# sensorBoard.net
KiCad netlist of a schematic drawn in EAGLE
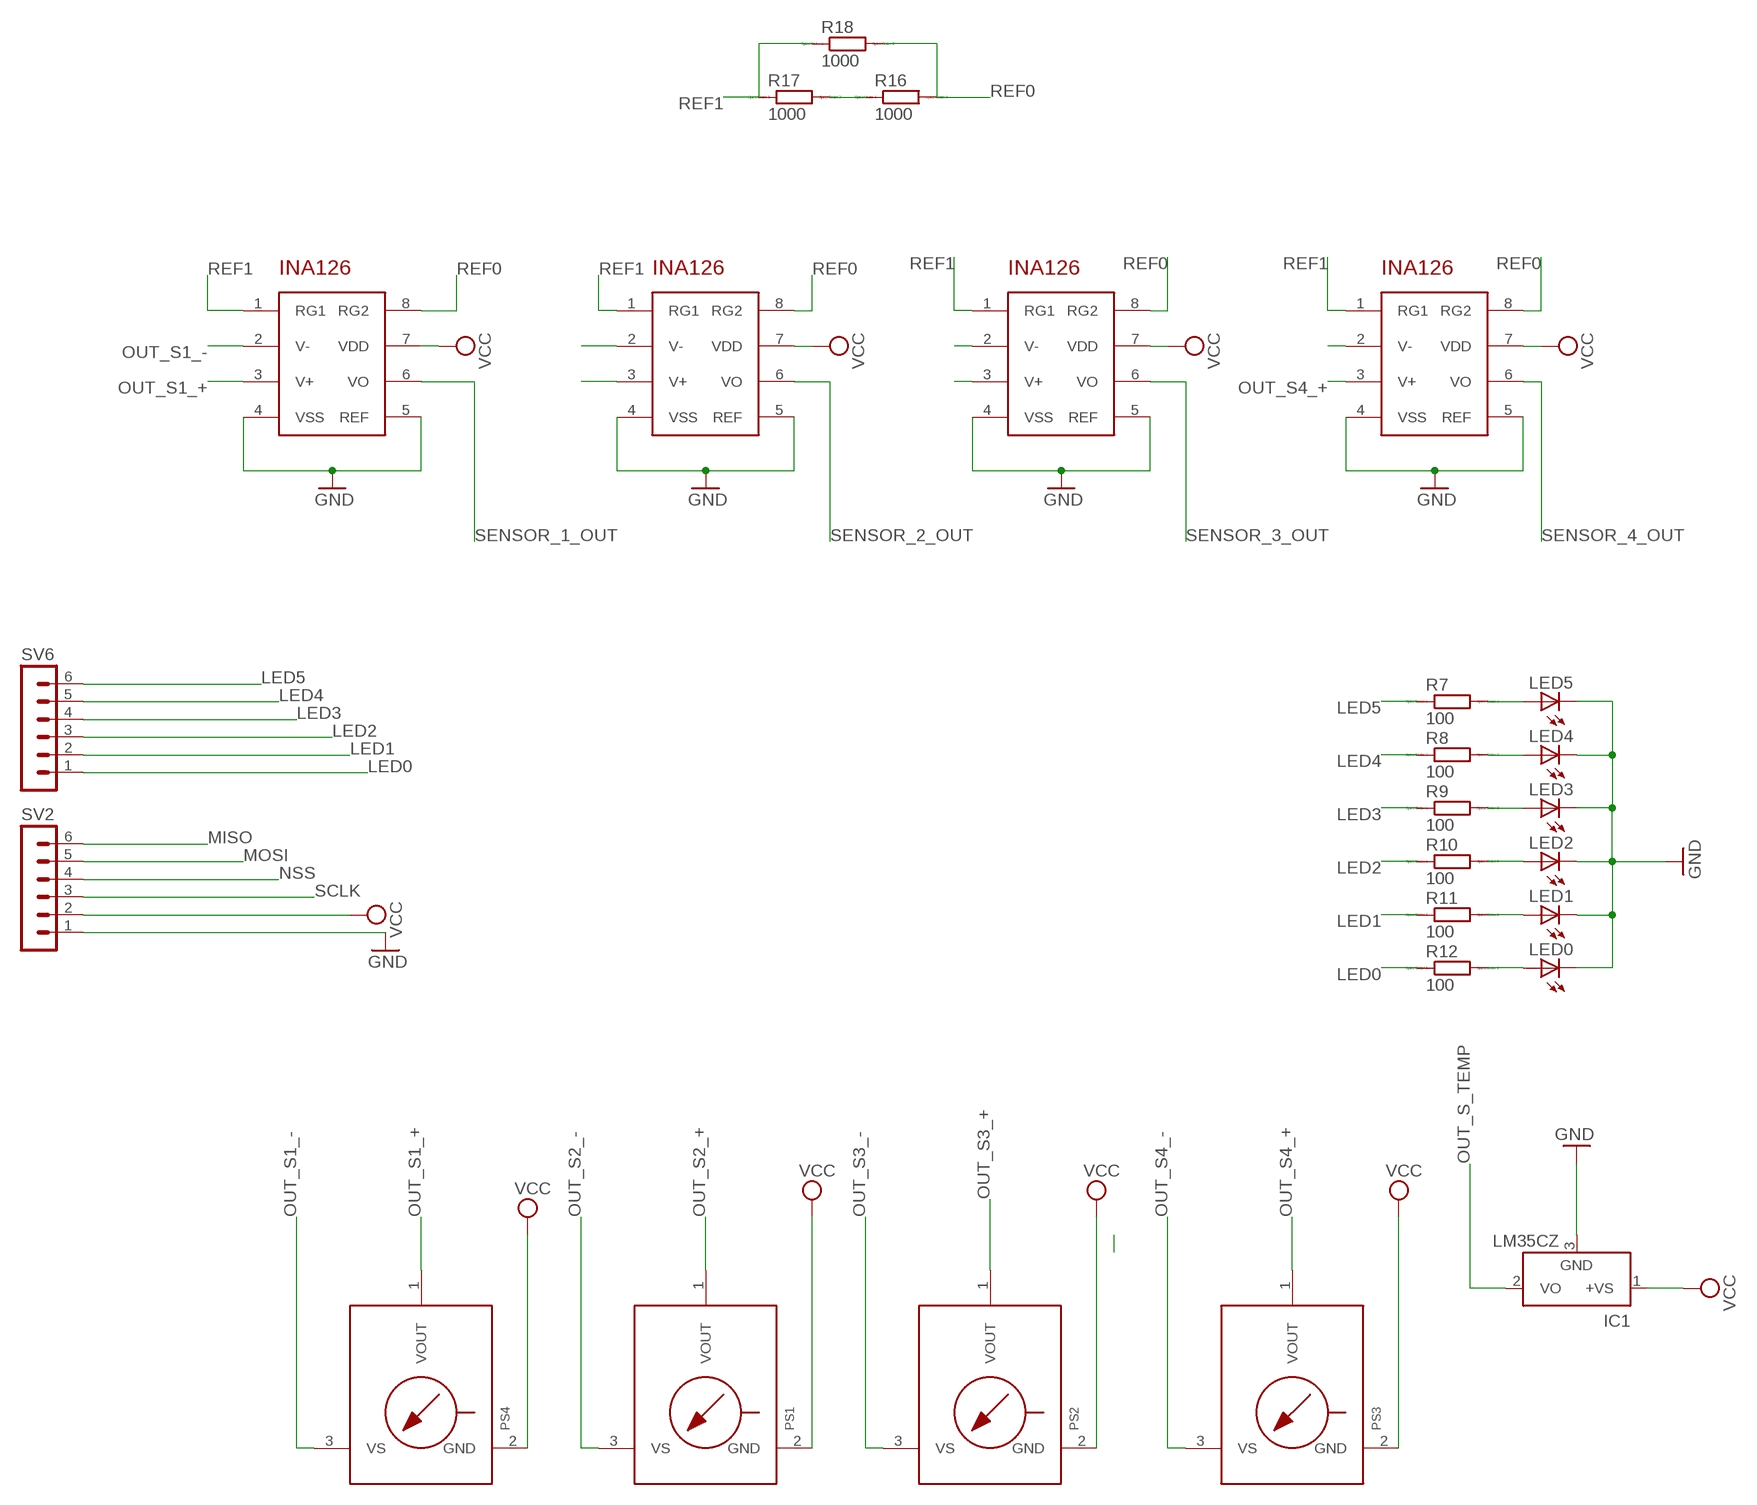
[diagram p0: schematic, sheet 1]

(export (version "E")
  (design (tool "Eeschema 10.0.6"))
  (components
    (comp (ref "IC1")
      (value "LM35CZ")
      (footprint "eagle-import:TO92")
      (libsource (lib "eagle-import") (part "LM35CZ"))
    )
    (comp (ref "LED0")
      (value "LED3MM")
      (footprint "eagle-import:LED3MM")
      (libsource (lib "eagle-import") (part "LED3MM"))
    )
    (comp (ref "LED1")
      (value "LED3MM")
      (footprint "eagle-import:LED3MM")
      (libsource (lib "eagle-import") (part "LED3MM"))
    )
    (comp (ref "LED2")
      (value "LED3MM")
      (footprint "eagle-import:LED3MM")
      (libsource (lib "eagle-import") (part "LED3MM"))
    )
    (comp (ref "LED3")
      (value "LED3MM")
      (footprint "eagle-import:LED3MM")
      (libsource (lib "eagle-import") (part "LED3MM"))
    )
    (comp (ref "LED4")
      (value "LED3MM")
      (footprint "eagle-import:LED3MM")
      (libsource (lib "eagle-import") (part "LED3MM"))
    )
    (comp (ref "LED5")
      (value "LED3MM")
      (footprint "eagle-import:LED3MM")
      (libsource (lib "eagle-import") (part "LED3MM"))
    )
    (comp (ref "PS1")
      (value "MPX-867B-H")
      (footprint "eagle-import:867B-H")
      (libsource (lib "eagle-import") (part "MPX-867B-H"))
    )
    (comp (ref "PS2")
      (value "MPX-867B-H")
      (footprint "eagle-import:867B-H")
      (libsource (lib "eagle-import") (part "MPX-867B-H"))
    )
    (comp (ref "PS3")
      (value "MPX-867B-H")
      (footprint "eagle-import:867B-H")
      (libsource (lib "eagle-import") (part "MPX-867B-H"))
    )
    (comp (ref "PS4")
      (value "MPX-867B-H")
      (footprint "eagle-import:867B-H")
      (libsource (lib "eagle-import") (part "MPX-867B-H"))
    )
    (comp (ref "R7")
      (value "100")
      (footprint "eagle-import:0207_10")
      (libsource (lib "eagle-import") (part "R0207/10"))
    )
    (comp (ref "R8")
      (value "100")
      (footprint "eagle-import:0207_10")
      (libsource (lib "eagle-import") (part "R0207/10"))
    )
    (comp (ref "R9")
      (value "100")
      (footprint "eagle-import:0207_10")
      (libsource (lib "eagle-import") (part "R0207/10"))
    )
    (comp (ref "R10")
      (value "100")
      (footprint "eagle-import:0207_10")
      (libsource (lib "eagle-import") (part "R0207/10"))
    )
    (comp (ref "R11")
      (value "100")
      (footprint "eagle-import:0207_10")
      (libsource (lib "eagle-import") (part "R0207/10"))
    )
    (comp (ref "R12")
      (value "100")
      (footprint "eagle-import:0207_10")
      (libsource (lib "eagle-import") (part "R0207/10"))
    )
    (comp (ref "R16")
      (value "1000")
      (footprint "eagle-import:0207_10")
      (libsource (lib "eagle-import") (part "R0207/10"))
    )
    (comp (ref "R17")
      (value "1000")
      (footprint "eagle-import:0207_10")
      (libsource (lib "eagle-import") (part "R0207/10"))
    )
    (comp (ref "R18")
      (value "1000")
      (footprint "eagle-import:0207_10")
      (libsource (lib "eagle-import") (part "R0207/10"))
    )
    (comp (ref "SV2")
      (value "MA06-1")
      (footprint "eagle-import:MA06-1")
      (libsource (lib "eagle-import") (part "MA06-1"))
    )
    (comp (ref "SV6")
      (value "MA06-1")
      (footprint "eagle-import:MA06-1")
      (libsource (lib "eagle-import") (part "MA06-1"))
    )
    (comp (ref "U$1")
      (value "INA126")
      (footprint "eagle-import:SO-08")
      (libsource (lib "eagle-import") (part "INA126"))
    )
    (comp (ref "U$2")
      (value "INA126")
      (footprint "eagle-import:SO-08")
      (libsource (lib "eagle-import") (part "INA126"))
    )
    (comp (ref "U$3")
      (value "INA126")
      (footprint "eagle-import:SO-08")
      (libsource (lib "eagle-import") (part "INA126"))
    )
    (comp (ref "U$4")
      (value "INA126")
      (footprint "eagle-import:SO-08")
      (libsource (lib "eagle-import") (part "INA126"))
    )
  )
  (nets
    (net (code "1") (name "/LED0") (class "Default")
      (node (ref "R12") (pin "1") (pinfunction "1_1") (pintype "passive"))
      (node (ref "SV6") (pin "1") (pinfunction "1_1") (pintype "passive"))
    )
    (net (code "2") (name "/LED1") (class "Default")
      (node (ref "R11") (pin "1") (pinfunction "1_1") (pintype "passive"))
      (node (ref "SV6") (pin "2") (pinfunction "2_2") (pintype "passive"))
    )
    (net (code "3") (name "/LED2") (class "Default")
      (node (ref "R10") (pin "1") (pinfunction "1_1") (pintype "passive"))
      (node (ref "SV6") (pin "3") (pinfunction "3_3") (pintype "passive"))
    )
    (net (code "4") (name "/LED3") (class "Default")
      (node (ref "R9") (pin "1") (pinfunction "1_1") (pintype "passive"))
      (node (ref "SV6") (pin "4") (pinfunction "4_4") (pintype "passive"))
    )
    (net (code "5") (name "/LED4") (class "Default")
      (node (ref "R8") (pin "1") (pinfunction "1_1") (pintype "passive"))
      (node (ref "SV6") (pin "5") (pinfunction "5_5") (pintype "passive"))
    )
    (net (code "6") (name "/LED5") (class "Default")
      (node (ref "R7") (pin "1") (pinfunction "1_1") (pintype "passive"))
      (node (ref "SV6") (pin "6") (pinfunction "6_6") (pintype "passive"))
    )
    (net (code "7") (name "/MISO") (class "Default")
      (node (ref "SV2") (pin "6") (pinfunction "6_6") (pintype "passive"))
    )
    (net (code "8") (name "/MOSI") (class "Default")
      (node (ref "SV2") (pin "5") (pinfunction "5_5") (pintype "passive"))
    )
    (net (code "9") (name "/NSS") (class "Default")
      (node (ref "SV2") (pin "4") (pinfunction "4_4") (pintype "passive"))
    )
    (net (code "10") (name "/OUT_S1_+") (class "Default")
      (node (ref "PS4") (pin "1") (pinfunction "VOUT_1") (pintype "output"))
    )
    (net (code "11") (name "/OUT_S1_-") (class "Default")
      (node (ref "PS4") (pin "3") (pinfunction "VS_3") (pintype "power_in"))
    )
    (net (code "12") (name "/OUT_S2_+") (class "Default")
      (node (ref "PS1") (pin "1") (pinfunction "VOUT_1") (pintype "output"))
    )
    (net (code "13") (name "/OUT_S2_-") (class "Default")
      (node (ref "PS1") (pin "3") (pinfunction "VS_3") (pintype "power_in"))
    )
    (net (code "14") (name "/OUT_S3_+") (class "Default")
      (node (ref "PS2") (pin "1") (pinfunction "VOUT_1") (pintype "output"))
    )
    (net (code "15") (name "/OUT_S3_-") (class "Default")
      (node (ref "PS2") (pin "3") (pinfunction "VS_3") (pintype "power_in"))
    )
    (net (code "16") (name "/OUT_S4_+") (class "Default")
      (node (ref "PS3") (pin "1") (pinfunction "VOUT_1") (pintype "output"))
    )
    (net (code "17") (name "/OUT_S4_-") (class "Default")
      (node (ref "PS3") (pin "3") (pinfunction "VS_3") (pintype "power_in"))
    )
    (net (code "18") (name "/OUT_S_TEMP") (class "Default")
      (node (ref "IC1") (pin "2") (pinfunction "VO_2") (pintype "input"))
    )
    (net (code "19") (name "/REF0") (class "Default")
      (node (ref "R16") (pin "2") (pinfunction "2_2") (pintype "passive"))
      (node (ref "R18") (pin "2") (pinfunction "2_2") (pintype "passive"))
    )
    (net (code "20") (name "/REF1") (class "Default")
      (node (ref "R17") (pin "1") (pinfunction "1_1") (pintype "passive"))
      (node (ref "R18") (pin "1") (pinfunction "1_1") (pintype "passive"))
    )
    (net (code "21") (name "/SCLK") (class "Default")
      (node (ref "SV2") (pin "3") (pinfunction "3_3") (pintype "passive"))
    )
    (net (code "22") (name "/SENSOR_1_OUT") (class "Default")
      (node (ref "U$4") (pin "6") (pinfunction "VO_6") (pintype "bidirectional"))
    )
    (net (code "23") (name "/SENSOR_2_OUT") (class "Default")
      (node (ref "U$1") (pin "6") (pinfunction "VO_6") (pintype "bidirectional"))
    )
    (net (code "24") (name "/SENSOR_3_OUT") (class "Default")
      (node (ref "U$2") (pin "6") (pinfunction "VO_6") (pintype "bidirectional"))
    )
    (net (code "25") (name "/SENSOR_4_OUT") (class "Default")
      (node (ref "U$3") (pin "6") (pinfunction "VO_6") (pintype "bidirectional"))
    )
    (net (code "26") (name "GND") (class "Default")
      (node (ref "IC1") (pin "3") (pinfunction "GND_3") (pintype "power_in"))
      (node (ref "LED0") (pin "K") (pinfunction "C_K") (pintype "passive"))
      (node (ref "LED1") (pin "K") (pinfunction "C_K") (pintype "passive"))
      (node (ref "LED2") (pin "K") (pinfunction "C_K") (pintype "passive"))
      (node (ref "LED3") (pin "K") (pinfunction "C_K") (pintype "passive"))
      (node (ref "LED4") (pin "K") (pinfunction "C_K") (pintype "passive"))
      (node (ref "LED5") (pin "K") (pinfunction "C_K") (pintype "passive"))
      (node (ref "SV2") (pin "1") (pinfunction "1_1") (pintype "passive"))
      (node (ref "U$1") (pin "4") (pinfunction "VSS_4") (pintype "bidirectional"))
      (node (ref "U$1") (pin "5") (pinfunction "REF_5") (pintype "bidirectional"))
      (node (ref "U$2") (pin "4") (pinfunction "VSS_4") (pintype "bidirectional"))
      (node (ref "U$2") (pin "5") (pinfunction "REF_5") (pintype "bidirectional"))
      (node (ref "U$3") (pin "4") (pinfunction "VSS_4") (pintype "bidirectional"))
      (node (ref "U$3") (pin "5") (pinfunction "REF_5") (pintype "bidirectional"))
      (node (ref "U$4") (pin "4") (pinfunction "VSS_4") (pintype "bidirectional"))
      (node (ref "U$4") (pin "5") (pinfunction "REF_5") (pintype "bidirectional"))
    )
    (net (code "27") (name "Net-(LED0-PadA)") (class "Default")
      (node (ref "LED0") (pin "A") (pinfunction "A_A") (pintype "passive"))
      (node (ref "R12") (pin "2") (pinfunction "2_2") (pintype "passive"))
    )
    (net (code "28") (name "Net-(LED1-PadA)") (class "Default")
      (node (ref "LED1") (pin "A") (pinfunction "A_A") (pintype "passive"))
      (node (ref "R11") (pin "2") (pinfunction "2_2") (pintype "passive"))
    )
    (net (code "29") (name "Net-(LED2-PadA)") (class "Default")
      (node (ref "LED2") (pin "A") (pinfunction "A_A") (pintype "passive"))
      (node (ref "R10") (pin "2") (pinfunction "2_2") (pintype "passive"))
    )
    (net (code "30") (name "Net-(LED3-PadA)") (class "Default")
      (node (ref "LED3") (pin "A") (pinfunction "A_A") (pintype "passive"))
      (node (ref "R9") (pin "2") (pinfunction "2_2") (pintype "passive"))
    )
    (net (code "31") (name "Net-(LED4-PadA)") (class "Default")
      (node (ref "LED4") (pin "A") (pinfunction "A_A") (pintype "passive"))
      (node (ref "R8") (pin "2") (pinfunction "2_2") (pintype "passive"))
    )
    (net (code "32") (name "Net-(LED5-PadA)") (class "Default")
      (node (ref "LED5") (pin "A") (pinfunction "A_A") (pintype "passive"))
      (node (ref "R7") (pin "2") (pinfunction "2_2") (pintype "passive"))
    )
    (net (code "33") (name "Net-(R16-Pad1)") (class "Default")
      (node (ref "R16") (pin "1") (pinfunction "1_1") (pintype "passive"))
      (node (ref "R17") (pin "2") (pinfunction "2_2") (pintype "passive"))
    )
    (net (code "34") (name "VCC") (class "Default")
      (node (ref "IC1") (pin "1") (pinfunction "+VS_1") (pintype "input"))
      (node (ref "PS1") (pin "2") (pinfunction "GND_2") (pintype "power_in"))
      (node (ref "PS2") (pin "2") (pinfunction "GND_2") (pintype "power_in"))
      (node (ref "PS3") (pin "2") (pinfunction "GND_2") (pintype "power_in"))
      (node (ref "PS4") (pin "2") (pinfunction "GND_2") (pintype "power_in"))
      (node (ref "SV2") (pin "2") (pinfunction "2_2") (pintype "passive"))
      (node (ref "U$1") (pin "7") (pinfunction "VDD_7") (pintype "bidirectional"))
      (node (ref "U$2") (pin "7") (pinfunction "VDD_7") (pintype "bidirectional"))
      (node (ref "U$3") (pin "7") (pinfunction "VDD_7") (pintype "bidirectional"))
      (node (ref "U$4") (pin "7") (pinfunction "VDD_7") (pintype "bidirectional"))
    )
    (net (code "35") (name "unconnected-(PS1-NC-Pad4)") (class "Default")
      (node (ref "PS1") (pin "4") (pinfunction "NC_4") (pintype "no_connect"))
    )
    (net (code "36") (name "unconnected-(PS1-NC-Pad5)") (class "Default")
      (node (ref "PS1") (pin "5") (pinfunction "NC_5") (pintype "no_connect"))
    )
    (net (code "37") (name "unconnected-(PS1-NC-Pad6)") (class "Default")
      (node (ref "PS1") (pin "6") (pinfunction "NC_6") (pintype "no_connect"))
    )
    (net (code "38") (name "unconnected-(PS2-NC-Pad4)") (class "Default")
      (node (ref "PS2") (pin "4") (pinfunction "NC_4") (pintype "no_connect"))
    )
    (net (code "39") (name "unconnected-(PS2-NC-Pad5)") (class "Default")
      (node (ref "PS2") (pin "5") (pinfunction "NC_5") (pintype "no_connect"))
    )
    (net (code "40") (name "unconnected-(PS2-NC-Pad6)") (class "Default")
      (node (ref "PS2") (pin "6") (pinfunction "NC_6") (pintype "no_connect"))
    )
    (net (code "41") (name "unconnected-(PS3-NC-Pad4)") (class "Default")
      (node (ref "PS3") (pin "4") (pinfunction "NC_4") (pintype "no_connect"))
    )
    (net (code "42") (name "unconnected-(PS3-NC-Pad5)") (class "Default")
      (node (ref "PS3") (pin "5") (pinfunction "NC_5") (pintype "no_connect"))
    )
    (net (code "43") (name "unconnected-(PS3-NC-Pad6)") (class "Default")
      (node (ref "PS3") (pin "6") (pinfunction "NC_6") (pintype "no_connect"))
    )
    (net (code "44") (name "unconnected-(PS4-NC-Pad4)") (class "Default")
      (node (ref "PS4") (pin "4") (pinfunction "NC_4") (pintype "no_connect"))
    )
    (net (code "45") (name "unconnected-(PS4-NC-Pad5)") (class "Default")
      (node (ref "PS4") (pin "5") (pinfunction "NC_5") (pintype "no_connect"))
    )
    (net (code "46") (name "unconnected-(PS4-NC-Pad6)") (class "Default")
      (node (ref "PS4") (pin "6") (pinfunction "NC_6") (pintype "no_connect"))
    )
    (net (code "47") (name "unconnected-(U$1-RG1-Pad1)") (class "Default")
      (node (ref "U$1") (pin "1") (pinfunction "RG1_1") (pintype "bidirectional"))
    )
    (net (code "48") (name "unconnected-(U$1-RG2-Pad8)") (class "Default")
      (node (ref "U$1") (pin "8") (pinfunction "RG2_8") (pintype "bidirectional"))
    )
    (net (code "49") (name "unconnected-(U$1-V+-Pad3)") (class "Default")
      (node (ref "U$1") (pin "3") (pinfunction "V+_3") (pintype "bidirectional"))
    )
    (net (code "50") (name "unconnected-(U$1-V--Pad2)") (class "Default")
      (node (ref "U$1") (pin "2") (pinfunction "V-_2") (pintype "bidirectional"))
    )
    (net (code "51") (name "unconnected-(U$2-RG1-Pad1)") (class "Default")
      (node (ref "U$2") (pin "1") (pinfunction "RG1_1") (pintype "bidirectional"))
    )
    (net (code "52") (name "unconnected-(U$2-RG2-Pad8)") (class "Default")
      (node (ref "U$2") (pin "8") (pinfunction "RG2_8") (pintype "bidirectional"))
    )
    (net (code "53") (name "unconnected-(U$2-V+-Pad3)") (class "Default")
      (node (ref "U$2") (pin "3") (pinfunction "V+_3") (pintype "bidirectional"))
    )
    (net (code "54") (name "unconnected-(U$2-V--Pad2)") (class "Default")
      (node (ref "U$2") (pin "2") (pinfunction "V-_2") (pintype "bidirectional"))
    )
    (net (code "55") (name "unconnected-(U$3-RG1-Pad1)") (class "Default")
      (node (ref "U$3") (pin "1") (pinfunction "RG1_1") (pintype "bidirectional"))
    )
    (net (code "56") (name "unconnected-(U$3-RG2-Pad8)") (class "Default")
      (node (ref "U$3") (pin "8") (pinfunction "RG2_8") (pintype "bidirectional"))
    )
    (net (code "57") (name "unconnected-(U$3-V+-Pad3)") (class "Default")
      (node (ref "U$3") (pin "3") (pinfunction "V+_3") (pintype "bidirectional"))
    )
    (net (code "58") (name "unconnected-(U$3-V--Pad2)") (class "Default")
      (node (ref "U$3") (pin "2") (pinfunction "V-_2") (pintype "bidirectional"))
    )
    (net (code "59") (name "unconnected-(U$4-RG1-Pad1)") (class "Default")
      (node (ref "U$4") (pin "1") (pinfunction "RG1_1") (pintype "bidirectional"))
    )
    (net (code "60") (name "unconnected-(U$4-RG2-Pad8)") (class "Default")
      (node (ref "U$4") (pin "8") (pinfunction "RG2_8") (pintype "bidirectional"))
    )
    (net (code "61") (name "unconnected-(U$4-V+-Pad3)") (class "Default")
      (node (ref "U$4") (pin "3") (pinfunction "V+_3") (pintype "bidirectional"))
    )
    (net (code "62") (name "unconnected-(U$4-V--Pad2)") (class "Default")
      (node (ref "U$4") (pin "2") (pinfunction "V-_2") (pintype "bidirectional"))
    )
  )
)
